# SdCard.net
KiCad netlist of a schematic drawn in Altium Designer
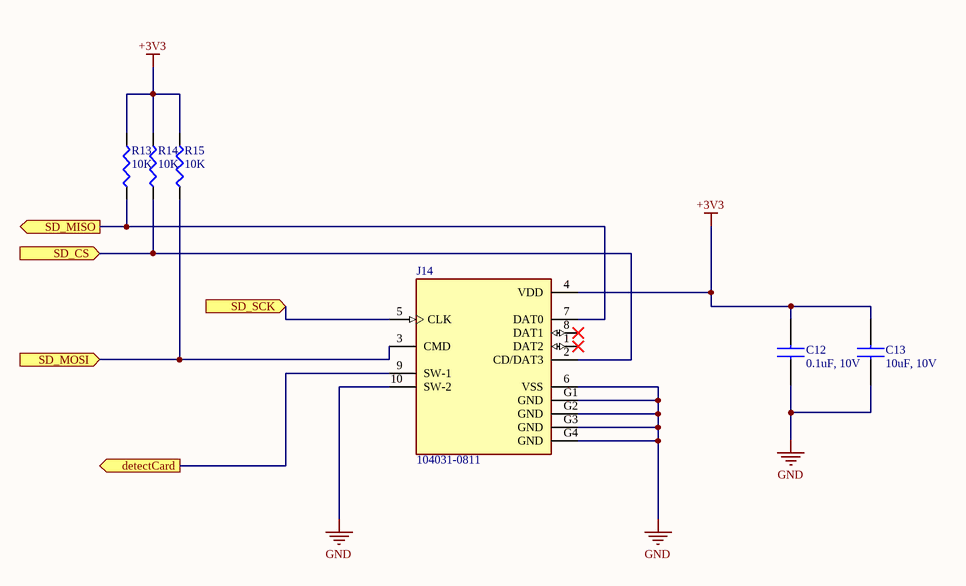
[diagram p0: SdCard.SchDoc]

(export (version "E")
  (design (tool "Eeschema 10.0.6"))
  (components
    (comp (ref "C12")
      (value "0.1uF, 10V")
      (footprint "SamacSys:CAPC1608X90N")
      (description "CAP CER 0.1UF 10V X7R 0603")
      (fields
        (field (name "MANUFACTURER_PART_NUMBER") "C0603C104K8RACTU")
        (field (name "MOUSER PART NUMBER") "187-CL10A106MP8NNNC")
      )
      (libsource (lib "SchlibpolyESP") (part "C0603C104K8RACTU"))
    )
    (comp (ref "C13")
      (value "10uF, 10V")
      (footprint "SamacSys:CAPC1608X90N")
      (description "CAP CER 10UF 10V X5R 0603")
      (fields
        (field (name "MANUFACTURER_PART_NUMBER") "CL10A106MP8NNNC")
        (field (name "MOUSER PART NUMBER") "187-CL10A106MP8NNNC")
      )
      (libsource (lib "SchlibpolyESP") (part "CL10A106MP8NNNC"))
    )
    (comp (ref "J14")
      (value "104031-0811")
      (footprint "MOLEX_104031-0811")
      (description "Surface Mount Micro SD Card Connector, with Push In Termination ¦ Molex Incorporated 104031-0811")
      (fields (field (name "MF") "Molex"))
      (libsource (lib "SchlibpolyESP") (part "104031-0811"))
    )
    (comp (ref "R13")
      (value "10K")
      (footprint "RESC1607X60N")
      (description "RES 10K OHM 5% 1/10W 0603")
      (fields
        (field (name "MANUFACTURER") "Yageo")
        (field (name "MANUFACTURER PART NUMBER") "RC0603JR-0710KL")
      )
      (libsource (lib "SchlibpolyESP") (part "RC0603JR-0710KL"))
    )
    (comp (ref "R14")
      (value "10K")
      (footprint "RESC1607X60N")
      (description "RES 10K OHM 5% 1/10W 0603")
      (fields
        (field (name "MANUFACTURER") "Yageo")
        (field (name "MANUFACTURER PART NUMBER") "RC0603JR-0710KL")
      )
      (libsource (lib "SchlibpolyESP") (part "RC0603JR-0710KL"))
    )
    (comp (ref "R15")
      (value "10K")
      (footprint "RESC1607X60N")
      (description "RES 10K OHM 5% 1/10W 0603")
      (fields
        (field (name "MANUFACTURER") "Yageo")
        (field (name "MANUFACTURER PART NUMBER") "RC0603JR-0710KL")
      )
      (libsource (lib "SchlibpolyESP") (part "RC0603JR-0710KL"))
    )
  )
  (nets
    (net (code "1") (name "+3V3") (class "Default")
      (node (ref "C12") (pin "2") (pinfunction "2_2") (pintype "passive"))
      (node (ref "C13") (pin "2") (pinfunction "2_2") (pintype "passive"))
      (node (ref "J14") (pin "4") (pinfunction "VDD_4") (pintype "power_in"))
      (node (ref "R13") (pin "2") (pinfunction "2_2") (pintype "passive"))
      (node (ref "R14") (pin "2") (pinfunction "2_2") (pintype "passive"))
      (node (ref "R15") (pin "2") (pinfunction "2_2") (pintype "passive"))
    )
    (net (code "2") (name "/SD_CS") (class "Default")
      (node (ref "J14") (pin "2") (pinfunction "CD/DAT3_2") (pintype "passive"))
      (node (ref "R14") (pin "1") (pinfunction "1_1") (pintype "passive"))
    )
    (net (code "3") (name "/SD_MISO") (class "Default")
      (node (ref "J14") (pin "7") (pinfunction "DAT0_7") (pintype "passive"))
      (node (ref "R13") (pin "1") (pinfunction "1_1") (pintype "passive"))
    )
    (net (code "4") (name "/SD_MOSI") (class "Default")
      (node (ref "J14") (pin "3") (pinfunction "CMD_3") (pintype "passive"))
      (node (ref "R15") (pin "1") (pinfunction "1_1") (pintype "passive"))
    )
    (net (code "5") (name "/SD_SCK") (class "Default")
      (node (ref "J14") (pin "5") (pinfunction "CLK_5") (pintype "input"))
    )
    (net (code "6") (name "/detectCard") (class "Default")
      (node (ref "J14") (pin "9") (pinfunction "SW-1_9") (pintype "passive"))
    )
    (net (code "7") (name "GND") (class "Default")
      (node (ref "C12") (pin "1") (pinfunction "1_1") (pintype "passive"))
      (node (ref "C13") (pin "1") (pinfunction "1_1") (pintype "passive"))
      (node (ref "J14") (pin "10") (pinfunction "SW-2_10") (pintype "passive"))
      (node (ref "J14") (pin "6") (pinfunction "VSS_6") (pintype "power_in"))
      (node (ref "J14") (pin "G1") (pinfunction "GND_G1") (pintype "power_in"))
      (node (ref "J14") (pin "G2") (pinfunction "GND_G2") (pintype "power_in"))
      (node (ref "J14") (pin "G3") (pinfunction "GND_G3") (pintype "power_in"))
      (node (ref "J14") (pin "G4") (pinfunction "GND_G4") (pintype "power_in"))
    )
    (net (code "8") (name "unconnected-(J14-DAT1-Pad8)") (class "Default")
      (node (ref "J14") (pin "8") (pinfunction "DAT1_8") (pintype "bidirectional+no_connect"))
    )
    (net (code "9") (name "unconnected-(J14-DAT2-Pad1)") (class "Default")
      (node (ref "J14") (pin "1") (pinfunction "DAT2_1") (pintype "bidirectional+no_connect"))
    )
  )
)
